# EEZ_DIB_BP3C_r3B2.net
KiCad netlist of a schematic drawn in EAGLE
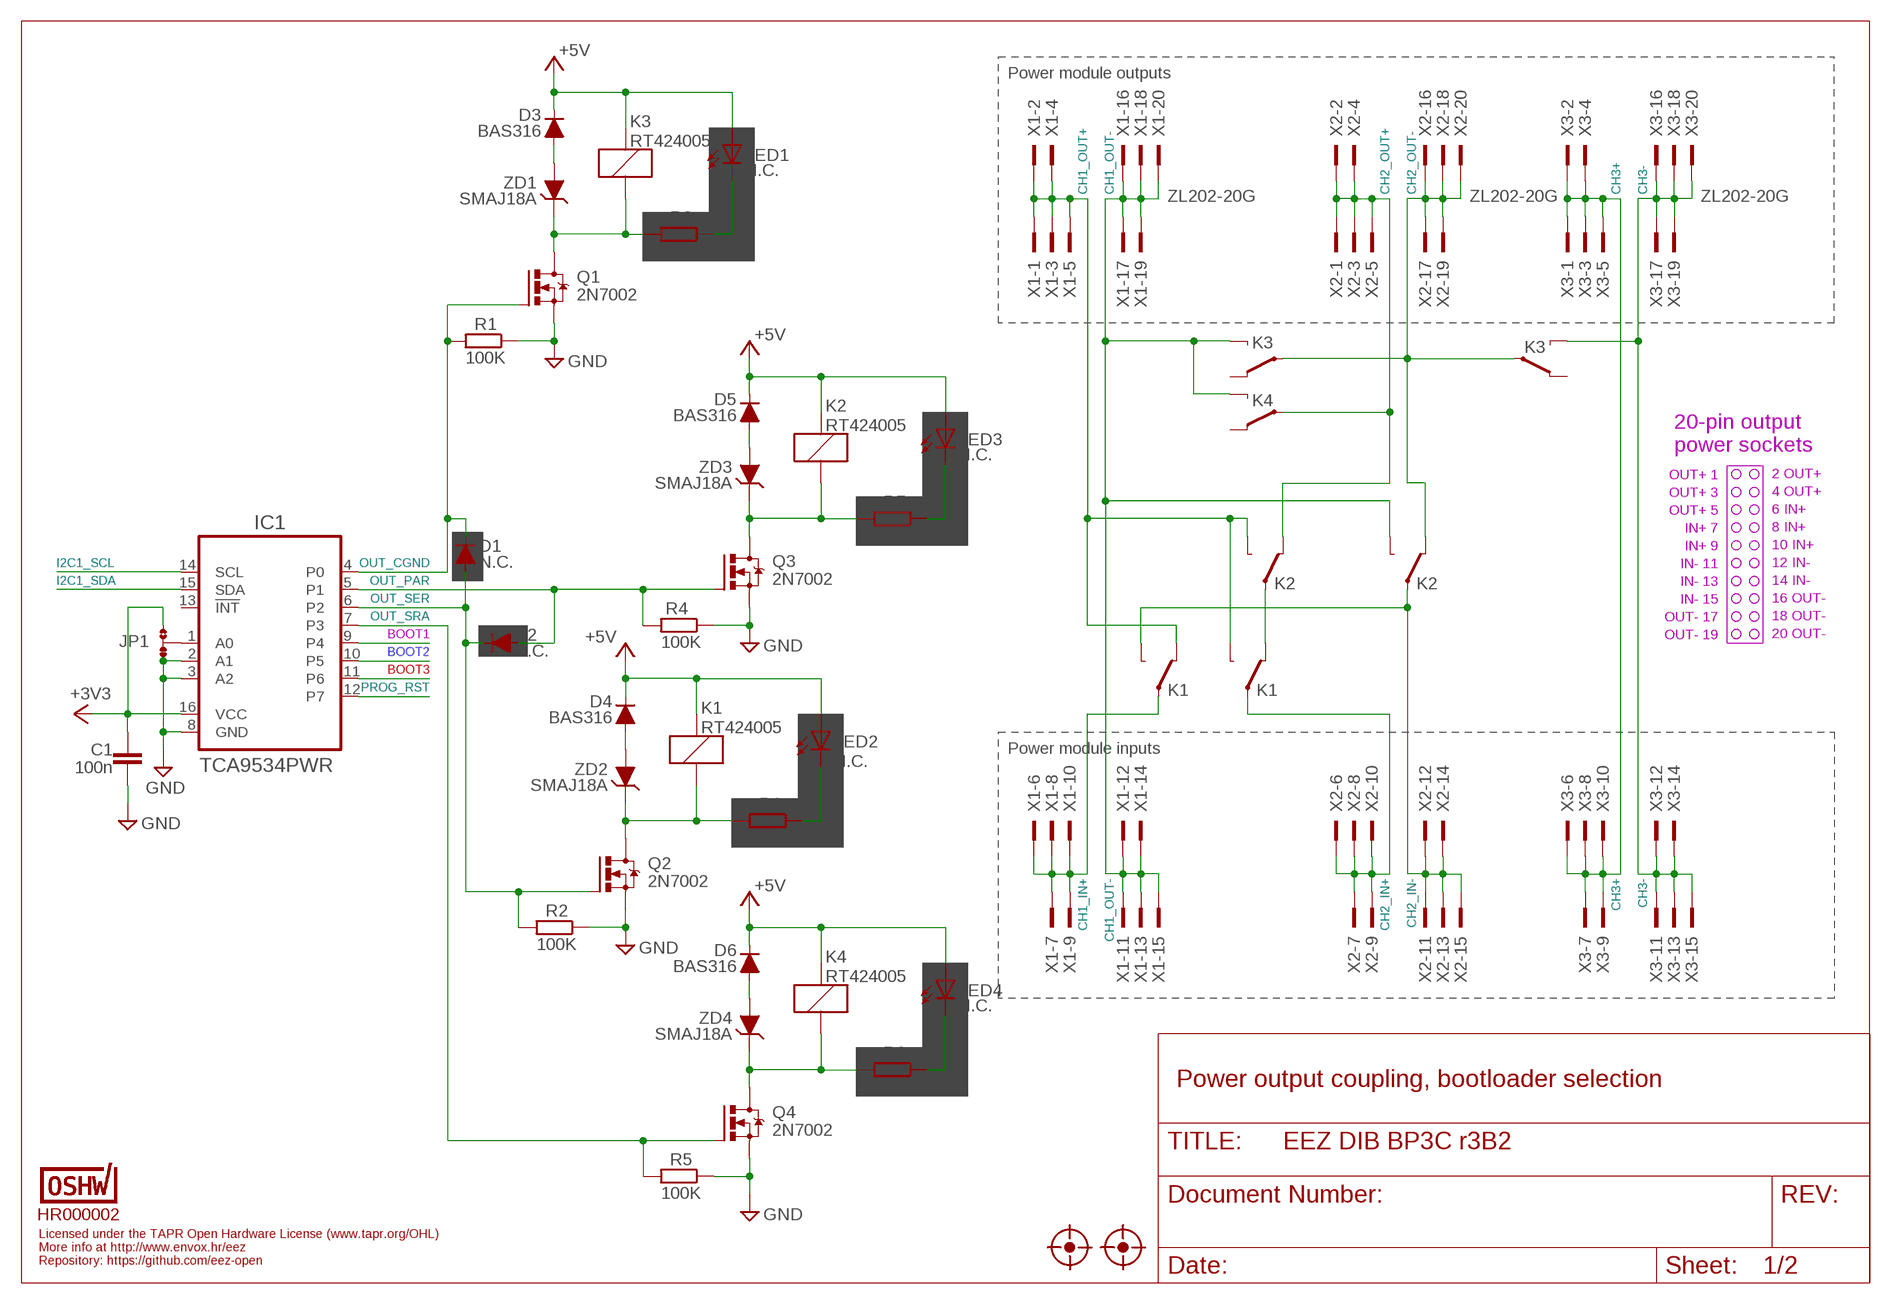
[diagram p0: schematic, sheet 1]
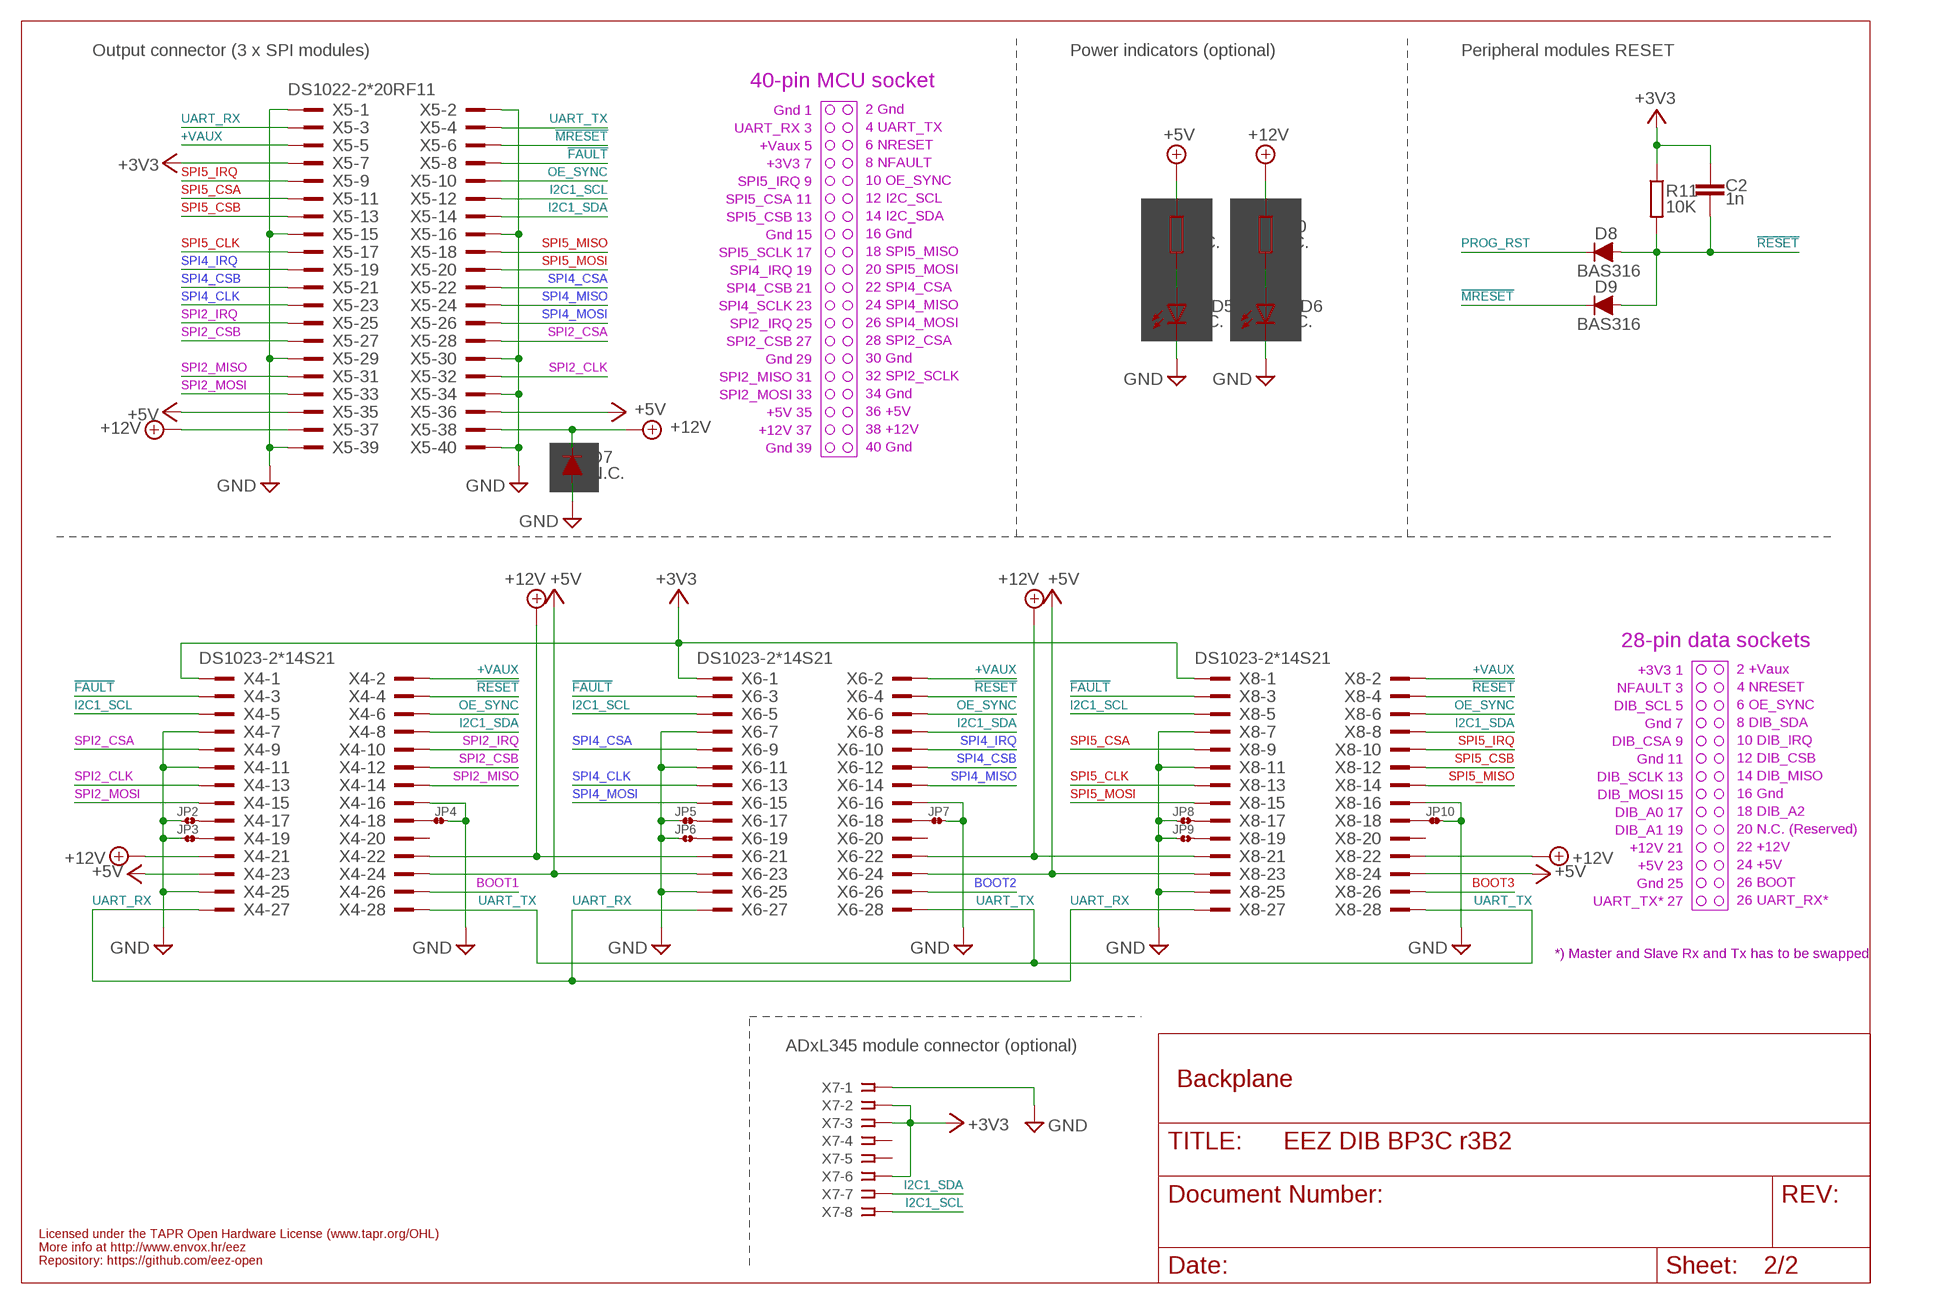
[diagram p1: schematic, sheet 2]

(export (version "E")
  (design (tool "Eeschema 10.0.6"))
  (components
    (comp (ref "C1")
      (value "100n")
      (footprint "eagle-import:C0603")
      (libsource (lib "eagle-import") (part "C-EUC0603"))
    )
    (comp (ref "D1")
      (value "N.C.")
      (footprint "eagle-import:SOD323-R")
      (libsource (lib "eagle-import") (part "DIODESOD323R"))
    )
    (comp (ref "D2")
      (value "N.C.")
      (footprint "eagle-import:SOD323-R")
      (libsource (lib "eagle-import") (part "DIODESOD323R"))
    )
    (comp (ref "D3")
      (value "BAS316")
      (footprint "eagle-import:SOD323-R")
      (libsource (lib "eagle-import") (part "DIODESOD323R"))
    )
    (comp (ref "D4")
      (value "BAS316")
      (footprint "eagle-import:SOD323-R")
      (libsource (lib "eagle-import") (part "DIODESOD323R"))
    )
    (comp (ref "D5")
      (value "BAS316")
      (footprint "eagle-import:SOD323-R")
      (libsource (lib "eagle-import") (part "DIODESOD323R"))
    )
    (comp (ref "D6")
      (value "BAS316")
      (footprint "eagle-import:SOD323-R")
      (libsource (lib "eagle-import") (part "DIODESOD323R"))
    )
    (comp (ref "FM1")
      (value "FIDUCIAL")
      (footprint "eagle-import:FIDUCIAL")
      (libsource (lib "eagle-import") (part "FIDUCIAL"))
    )
    (comp (ref "FM2")
      (value "FIDUCIAL")
      (footprint "eagle-import:FIDUCIAL")
      (libsource (lib "eagle-import") (part "FIDUCIAL"))
    )
    (comp (ref "IC1")
      (value "TCA9534PWR")
      (footprint "eagle-import:PW(R-PDSO-G16)")
      (libsource (lib "eagle-import") (part "TCA9534PWR"))
    )
    (comp (ref "JP1")
      (value "JP3-CUT")
      (footprint "eagle-import:JP3-CUT")
      (libsource (lib "eagle-import") (part "JP3-CUT"))
    )
    (comp (ref "K1")
      (value "RT424005")
      (footprint "eagle-import:RT-C_016A5_ROUND")
      (libsource (lib "eagle-import") (part "RELAY_RT314012-2"))
    )
    (comp (ref "K2")
      (value "RT424005")
      (footprint "eagle-import:RT-C_016A5_ROUND")
      (libsource (lib "eagle-import") (part "RELAY_RT314012-2"))
    )
    (comp (ref "K3")
      (value "RT424005")
      (footprint "eagle-import:RT-C_016A5_ROUND")
      (libsource (lib "eagle-import") (part "RELAY_RT314012-2"))
    )
    (comp (ref "K4")
      (value "RT424005")
      (footprint "eagle-import:RT-C_016A5_ROUND")
      (libsource (lib "eagle-import") (part "RELAY_RT314012-2"))
    )
    (comp (ref "LED1")
      (value "N.C.")
      (footprint "eagle-import:LED_0805")
      (libsource (lib "eagle-import") (part "LED0805"))
    )
    (comp (ref "LED2")
      (value "N.C.")
      (footprint "eagle-import:LED_0805")
      (libsource (lib "eagle-import") (part "LED0805"))
    )
    (comp (ref "LED3")
      (value "N.C.")
      (footprint "eagle-import:LED_0805")
      (libsource (lib "eagle-import") (part "LED0805"))
    )
    (comp (ref "LED4")
      (value "N.C.")
      (footprint "eagle-import:LED_0805")
      (libsource (lib "eagle-import") (part "LED0805"))
    )
    (comp (ref "OSHWA")
      (value "HR000002")
      (footprint "eagle-import:CERT-SMALL-SILK")
      (libsource (lib "eagle-import") (part "OSHWA-CERT-SMALL"))
    )
    (comp (ref "Q1")
      (value "2N7002")
      (footprint "eagle-import:SOT103P240X110-3N")
      (fields
        (field (name "MPN") "2N7002-7-F")
        (field (name "MPN_1") "2N7002-7-F")
        (field (name "OC_FARNELL") "1713823")
        (field (name "OC_NEWARK") "25R5679")
        (field (name "PACKAGE") "SOT-23-3")
        (field (name "SUPPLIER") "DIODES INC.")
      )
      (libsource (lib "eagle-import") (part "2N7002"))
    )
    (comp (ref "Q2")
      (value "2N7002")
      (footprint "eagle-import:SOT103P240X110-3N")
      (fields
        (field (name "MPN") "2N7002-7-F")
        (field (name "MPN_1") "2N7002-7-F")
        (field (name "OC_FARNELL") "1713823")
        (field (name "OC_NEWARK") "25R5679")
        (field (name "PACKAGE") "SOT-23-3")
        (field (name "SUPPLIER") "DIODES INC.")
      )
      (libsource (lib "eagle-import") (part "2N7002"))
    )
    (comp (ref "Q3")
      (value "2N7002")
      (footprint "eagle-import:SOT103P240X110-3N")
      (fields
        (field (name "MPN") "2N7002-7-F")
        (field (name "MPN_1") "2N7002-7-F")
        (field (name "OC_FARNELL") "1713823")
        (field (name "OC_NEWARK") "25R5679")
        (field (name "PACKAGE") "SOT-23-3")
        (field (name "SUPPLIER") "DIODES INC.")
      )
      (libsource (lib "eagle-import") (part "2N7002"))
    )
    (comp (ref "Q4")
      (value "2N7002")
      (footprint "eagle-import:SOT103P240X110-3N")
      (fields
        (field (name "MPN") "2N7002-7-F")
        (field (name "MPN_1") "2N7002-7-F")
        (field (name "OC_FARNELL") "1713823")
        (field (name "OC_NEWARK") "25R5679")
        (field (name "PACKAGE") "SOT-23-3")
        (field (name "SUPPLIER") "DIODES INC.")
      )
      (libsource (lib "eagle-import") (part "2N7002"))
    )
    (comp (ref "R1")
      (value "100K")
      (footprint "eagle-import:R0805")
      (libsource (lib "eagle-import") (part "R-EU_R0805"))
    )
    (comp (ref "R2")
      (value "100K")
      (footprint "eagle-import:R0805")
      (libsource (lib "eagle-import") (part "R-EU_R0805"))
    )
    (comp (ref "R3")
      (value "N.C.")
      (footprint "eagle-import:R0805")
      (libsource (lib "eagle-import") (part "R-EU_R0805"))
    )
    (comp (ref "R4")
      (value "100K")
      (footprint "eagle-import:R0805")
      (libsource (lib "eagle-import") (part "R-EU_R0805"))
    )
    (comp (ref "R5")
      (value "100K")
      (footprint "eagle-import:R0805")
      (libsource (lib "eagle-import") (part "R-EU_R0805"))
    )
    (comp (ref "R6")
      (value "N.C.")
      (footprint "eagle-import:R0805")
      (libsource (lib "eagle-import") (part "R-EU_R0805"))
    )
    (comp (ref "R7")
      (value "N.C.")
      (footprint "eagle-import:R0805")
      (libsource (lib "eagle-import") (part "R-EU_R0805"))
    )
    (comp (ref "R8")
      (value "N.C.")
      (footprint "eagle-import:R0805")
      (libsource (lib "eagle-import") (part "R-EU_R0805"))
    )
    (comp (ref "X1")
      (value "ZL202-20G")
      (footprint "eagle-import:DS1021-2_10SF11")
      (libsource (lib "eagle-import") (part "DS1021-210SF11"))
    )
    (comp (ref "X2")
      (value "ZL202-20G")
      (footprint "eagle-import:DS1021-2_10SF11")
      (libsource (lib "eagle-import") (part "DS1021-210SF11"))
    )
    (comp (ref "X3")
      (value "ZL202-20G")
      (footprint "eagle-import:DS1021-2_10SF11")
      (libsource (lib "eagle-import") (part "DS1021-210SF11"))
    )
    (comp (ref "ZD1")
      (value "SMAJ18A")
      (footprint "eagle-import:DO214AC")
      (libsource (lib "eagle-import") (part "PSMAXX"))
    )
    (comp (ref "ZD2")
      (value "SMAJ18A")
      (footprint "eagle-import:DO214AC")
      (libsource (lib "eagle-import") (part "PSMAXX"))
    )
    (comp (ref "ZD3")
      (value "SMAJ18A")
      (footprint "eagle-import:DO214AC")
      (libsource (lib "eagle-import") (part "PSMAXX"))
    )
    (comp (ref "ZD4")
      (value "SMAJ18A")
      (footprint "eagle-import:DO214AC")
      (libsource (lib "eagle-import") (part "PSMAXX"))
    )
    (comp (ref "C2")
      (value "1n")
      (footprint "eagle-import:C0805")
      (libsource (lib "eagle-import") (part "C-EUC0805"))
    )
    (comp (ref "D7")
      (value "N.C.")
      (footprint "eagle-import:DO214AA")
      (libsource (lib "eagle-import") (part "MyLib6_DIODEDO214AA"))
    )
    (comp (ref "D8")
      (value "BAS316")
      (footprint "eagle-import:SOD323-R")
      (libsource (lib "eagle-import") (part "DIODESOD323R"))
    )
    (comp (ref "D9")
      (value "BAS316")
      (footprint "eagle-import:SOD323-R")
      (libsource (lib "eagle-import") (part "DIODESOD323R"))
    )
    (comp (ref "JP2")
      (value "JP2-CUT")
      (footprint "eagle-import:JP2-CUT")
      (libsource (lib "eagle-import") (part "JP2-CUT"))
    )
    (comp (ref "JP3")
      (value "JP2-NOCUT")
      (footprint "eagle-import:JP2-NOCUT")
      (libsource (lib "eagle-import") (part "JP2-NOCUT"))
    )
    (comp (ref "JP4")
      (value "JP2-NOCUT")
      (footprint "eagle-import:JP2-NOCUT")
      (libsource (lib "eagle-import") (part "JP2-NOCUT"))
    )
    (comp (ref "JP5")
      (value "JP2-NOCUT")
      (footprint "eagle-import:JP2-NOCUT")
      (libsource (lib "eagle-import") (part "JP2-NOCUT"))
    )
    (comp (ref "JP6")
      (value "JP2-CUT")
      (footprint "eagle-import:JP2-CUT")
      (libsource (lib "eagle-import") (part "JP2-CUT"))
    )
    (comp (ref "JP7")
      (value "JP2-NOCUT")
      (footprint "eagle-import:JP2-NOCUT")
      (libsource (lib "eagle-import") (part "JP2-NOCUT"))
    )
    (comp (ref "JP8")
      (value "JP2-CUT")
      (footprint "eagle-import:JP2-CUT")
      (libsource (lib "eagle-import") (part "JP2-CUT"))
    )
    (comp (ref "JP9")
      (value "JP2-CUT")
      (footprint "eagle-import:JP2-CUT")
      (libsource (lib "eagle-import") (part "JP2-CUT"))
    )
    (comp (ref "JP10")
      (value "JP2-NOCUT")
      (footprint "eagle-import:JP2-NOCUT")
      (libsource (lib "eagle-import") (part "JP2-NOCUT"))
    )
    (comp (ref "LED5")
      (value "N.C.")
      (footprint "eagle-import:LED_0805")
      (libsource (lib "eagle-import") (part "LED0805"))
    )
    (comp (ref "LED6")
      (value "N.C.")
      (footprint "eagle-import:LED_0805")
      (libsource (lib "eagle-import") (part "LED0805"))
    )
    (comp (ref "R9")
      (value "N.C.")
      (footprint "eagle-import:R0805")
      (libsource (lib "eagle-import") (part "R-EU_R0805"))
    )
    (comp (ref "R10")
      (value "N.C.")
      (footprint "eagle-import:R0805")
      (libsource (lib "eagle-import") (part "R-EU_R0805"))
    )
    (comp (ref "R11")
      (value "10K")
      (footprint "eagle-import:R0805")
      (libsource (lib "eagle-import") (part "R-EU_R0805"))
    )
    (comp (ref "X4")
      (value "DS1023-2*14S21")
      (footprint "eagle-import:TSW-114-07-F-D")
      (libsource (lib "eagle-import") (part "TSW-114-07-F-D"))
    )
    (comp (ref "X5")
      (value "DS1022-2*20RF11")
      (footprint "eagle-import:ZL212-40KG")
      (libsource (lib "eagle-import") (part "ZL212-40KG"))
    )
    (comp (ref "X6")
      (value "DS1023-2*14S21")
      (footprint "eagle-import:TSW-114-07-F-D")
      (libsource (lib "eagle-import") (part "TSW-114-07-F-D"))
    )
    (comp (ref "X7")
      (value "N.C.")
      (footprint "eagle-import:SSW-108-02-S-S")
      (fields (field (name "MPN") "SSW-108-02-S-S"))
      (libsource (lib "eagle-import") (part "SSW-108-02-S-S"))
    )
    (comp (ref "X8")
      (value "DS1023-2*14S21")
      (footprint "eagle-import:TSW-114-07-F-D")
      (libsource (lib "eagle-import") (part "TSW-114-07-F-D"))
    )
  )
  (nets
    (net (code "1") (name "+3V3") (class "Default")
      (node (ref "C1") (pin "1") (pinfunction "1_1") (pintype "passive"))
      (node (ref "C2") (pin "2") (pinfunction "2_2") (pintype "passive"))
      (node (ref "IC1") (pin "16") (pinfunction "VCC_16") (pintype "passive"))
      (node (ref "JP1") (pin "NO") (pinfunction "NO_NO") (pintype "passive"))
      (node (ref "R11") (pin "1") (pinfunction "1_1") (pintype "passive"))
      (node (ref "X4") (pin "1") (pinfunction "1_1") (pintype "passive"))
      (node (ref "X5") (pin "7") (pinfunction "1_7") (pintype "passive"))
      (node (ref "X6") (pin "1") (pinfunction "1_1") (pintype "passive"))
      (node (ref "X7") (pin "2") (pinfunction "1_2") (pintype "passive"))
      (node (ref "X7") (pin "3") (pinfunction "1_3") (pintype "passive"))
      (node (ref "X7") (pin "6") (pinfunction "1_6") (pintype "passive"))
      (node (ref "X8") (pin "1") (pinfunction "1_1") (pintype "passive"))
    )
    (net (code "2") (name "+5V") (class "Default")
      (node (ref "D3") (pin "C") (pinfunction "C_C") (pintype "passive"))
      (node (ref "D4") (pin "C") (pinfunction "C_C") (pintype "passive"))
      (node (ref "D5") (pin "C") (pinfunction "C_C") (pintype "passive"))
      (node (ref "D6") (pin "C") (pinfunction "C_C") (pintype "passive"))
      (node (ref "K1") (pin "A2") (pinfunction "C1_A2") (pintype "passive"))
      (node (ref "K2") (pin "A2") (pinfunction "C1_A2") (pintype "passive"))
      (node (ref "K3") (pin "A2") (pinfunction "C1_A2") (pintype "passive"))
      (node (ref "K4") (pin "A2") (pinfunction "C1_A2") (pintype "passive"))
      (node (ref "LED1") (pin "A") (pinfunction "A_A") (pintype "passive"))
      (node (ref "LED2") (pin "A") (pinfunction "A_A") (pintype "passive"))
      (node (ref "LED3") (pin "A") (pinfunction "A_A") (pintype "passive"))
      (node (ref "LED4") (pin "A") (pinfunction "A_A") (pintype "passive"))
      (node (ref "R9") (pin "1") (pinfunction "1_1") (pintype "passive"))
      (node (ref "X4") (pin "23") (pinfunction "1_23") (pintype "passive"))
      (node (ref "X4") (pin "24") (pinfunction "1_24") (pintype "passive"))
      (node (ref "X5") (pin "35") (pinfunction "1_35") (pintype "passive"))
      (node (ref "X5") (pin "36") (pinfunction "1_36") (pintype "passive"))
      (node (ref "X6") (pin "23") (pinfunction "1_23") (pintype "passive"))
      (node (ref "X6") (pin "24") (pinfunction "1_24") (pintype "passive"))
      (node (ref "X8") (pin "23") (pinfunction "1_23") (pintype "passive"))
      (node (ref "X8") (pin "24") (pinfunction "1_24") (pintype "passive"))
    )
    (net (code "3") (name "+12V") (class "Default")
      (node (ref "D7") (pin "C") (pinfunction "C_C") (pintype "passive"))
      (node (ref "R10") (pin "1") (pinfunction "1_1") (pintype "passive"))
      (node (ref "X4") (pin "21") (pinfunction "1_21") (pintype "passive"))
      (node (ref "X4") (pin "22") (pinfunction "1_22") (pintype "passive"))
      (node (ref "X5") (pin "37") (pinfunction "1_37") (pintype "passive"))
      (node (ref "X5") (pin "38") (pinfunction "1_38") (pintype "passive"))
      (node (ref "X6") (pin "21") (pinfunction "1_21") (pintype "passive"))
      (node (ref "X6") (pin "22") (pinfunction "1_22") (pintype "passive"))
      (node (ref "X8") (pin "21") (pinfunction "1_21") (pintype "passive"))
      (node (ref "X8") (pin "22") (pinfunction "1_22") (pintype "passive"))
    )
    (net (code "4") (name "+VAUX") (class "Default")
      (node (ref "X4") (pin "2") (pinfunction "1_2") (pintype "passive"))
      (node (ref "X5") (pin "5") (pinfunction "1_5") (pintype "passive"))
      (node (ref "X6") (pin "2") (pinfunction "1_2") (pintype "passive"))
      (node (ref "X8") (pin "2") (pinfunction "1_2") (pintype "passive"))
    )
    (net (code "5") (name "BOOT1") (class "Default")
      (node (ref "IC1") (pin "9") (pinfunction "P4_9") (pintype "bidirectional"))
      (node (ref "X4") (pin "26") (pinfunction "1_26") (pintype "passive"))
    )
    (net (code "6") (name "BOOT2") (class "Default")
      (node (ref "IC1") (pin "10") (pinfunction "P5_10") (pintype "bidirectional"))
      (node (ref "X6") (pin "26") (pinfunction "1_26") (pintype "passive"))
    )
    (net (code "7") (name "BOOT3") (class "Default")
      (node (ref "IC1") (pin "11") (pinfunction "P6_11") (pintype "bidirectional"))
      (node (ref "X8") (pin "26") (pinfunction "1_26") (pintype "passive"))
    )
    (net (code "8") (name "CH1_IN+") (class "Default")
      (node (ref "K1") (pin "11A") (pinfunction "P_11A") (pintype "passive"))
      (node (ref "X1") (pin "10") (pinfunction "1_10") (pintype "passive"))
      (node (ref "X1") (pin "6") (pinfunction "1_6") (pintype "passive"))
      (node (ref "X1") (pin "7") (pinfunction "1_7") (pintype "passive"))
      (node (ref "X1") (pin "8") (pinfunction "1_8") (pintype "passive"))
      (node (ref "X1") (pin "9") (pinfunction "1_9") (pintype "passive"))
    )
    (net (code "9") (name "CH1_OUT+") (class "Default")
      (node (ref "K1") (pin "12A") (pinfunction "S_12A") (pintype "passive"))
      (node (ref "K1") (pin "14B") (pinfunction "O_14B") (pintype "passive"))
      (node (ref "K2") (pin "14A") (pinfunction "O_14A") (pintype "passive"))
      (node (ref "X1") (pin "1") (pinfunction "1_1") (pintype "passive"))
      (node (ref "X1") (pin "2") (pinfunction "1_2") (pintype "passive"))
      (node (ref "X1") (pin "3") (pinfunction "1_3") (pintype "passive"))
      (node (ref "X1") (pin "4") (pinfunction "1_4") (pintype "passive"))
      (node (ref "X1") (pin "5") (pinfunction "1_5") (pintype "passive"))
    )
    (net (code "10") (name "CH1_OUT-") (class "Default")
      (node (ref "K2") (pin "14B") (pinfunction "O_14B") (pintype "passive"))
      (node (ref "K3") (pin "14A") (pinfunction "O_14A") (pintype "passive"))
      (node (ref "K4") (pin "14A") (pinfunction "O_14A") (pintype "passive"))
      (node (ref "X1") (pin "11") (pinfunction "1_11") (pintype "passive"))
      (node (ref "X1") (pin "12") (pinfunction "1_12") (pintype "passive"))
      (node (ref "X1") (pin "13") (pinfunction "1_13") (pintype "passive"))
      (node (ref "X1") (pin "14") (pinfunction "1_14") (pintype "passive"))
      (node (ref "X1") (pin "15") (pinfunction "1_15") (pintype "passive"))
      (node (ref "X1") (pin "16") (pinfunction "1_16") (pintype "passive"))
      (node (ref "X1") (pin "17") (pinfunction "1_17") (pintype "passive"))
      (node (ref "X1") (pin "18") (pinfunction "1_18") (pintype "passive"))
      (node (ref "X1") (pin "19") (pinfunction "1_19") (pintype "passive"))
      (node (ref "X1") (pin "20") (pinfunction "1_20") (pintype "passive"))
    )
    (net (code "11") (name "CH2_IN+") (class "Default")
      (node (ref "K1") (pin "11B") (pinfunction "P_11B") (pintype "passive"))
      (node (ref "X2") (pin "10") (pinfunction "1_10") (pintype "passive"))
      (node (ref "X2") (pin "6") (pinfunction "1_6") (pintype "passive"))
      (node (ref "X2") (pin "7") (pinfunction "1_7") (pintype "passive"))
      (node (ref "X2") (pin "8") (pinfunction "1_8") (pintype "passive"))
      (node (ref "X2") (pin "9") (pinfunction "1_9") (pintype "passive"))
    )
    (net (code "12") (name "CH2_IN-") (class "Default")
      (node (ref "K1") (pin "14A") (pinfunction "O_14A") (pintype "passive"))
      (node (ref "K2") (pin "11B") (pinfunction "P_11B") (pintype "passive"))
      (node (ref "X2") (pin "11") (pinfunction "1_11") (pintype "passive"))
      (node (ref "X2") (pin "12") (pinfunction "1_12") (pintype "passive"))
      (node (ref "X2") (pin "13") (pinfunction "1_13") (pintype "passive"))
      (node (ref "X2") (pin "14") (pinfunction "1_14") (pintype "passive"))
      (node (ref "X2") (pin "15") (pinfunction "1_15") (pintype "passive"))
    )
    (net (code "13") (name "CH2_OUT+") (class "Default")
      (node (ref "K2") (pin "12A") (pinfunction "S_12A") (pintype "passive"))
      (node (ref "K4") (pin "11A") (pinfunction "P_11A") (pintype "passive"))
      (node (ref "X2") (pin "1") (pinfunction "1_1") (pintype "passive"))
      (node (ref "X2") (pin "2") (pinfunction "1_2") (pintype "passive"))
      (node (ref "X2") (pin "3") (pinfunction "1_3") (pintype "passive"))
      (node (ref "X2") (pin "4") (pinfunction "1_4") (pintype "passive"))
      (node (ref "X2") (pin "5") (pinfunction "1_5") (pintype "passive"))
    )
    (net (code "14") (name "CH2_OUT-") (class "Default")
      (node (ref "K2") (pin "12B") (pinfunction "S_12B") (pintype "passive"))
      (node (ref "K3") (pin "11A") (pinfunction "P_11A") (pintype "passive"))
      (node (ref "K3") (pin "11B") (pinfunction "P_11B") (pintype "passive"))
      (node (ref "X2") (pin "16") (pinfunction "1_16") (pintype "passive"))
      (node (ref "X2") (pin "17") (pinfunction "1_17") (pintype "passive"))
      (node (ref "X2") (pin "18") (pinfunction "1_18") (pintype "passive"))
      (node (ref "X2") (pin "19") (pinfunction "1_19") (pintype "passive"))
      (node (ref "X2") (pin "20") (pinfunction "1_20") (pintype "passive"))
    )
    (net (code "15") (name "CH3+") (class "Default")
      (node (ref "X3") (pin "1") (pinfunction "1_1") (pintype "passive"))
      (node (ref "X3") (pin "10") (pinfunction "1_10") (pintype "passive"))
      (node (ref "X3") (pin "2") (pinfunction "1_2") (pintype "passive"))
      (node (ref "X3") (pin "3") (pinfunction "1_3") (pintype "passive"))
      (node (ref "X3") (pin "4") (pinfunction "1_4") (pintype "passive"))
      (node (ref "X3") (pin "5") (pinfunction "1_5") (pintype "passive"))
      (node (ref "X3") (pin "6") (pinfunction "1_6") (pintype "passive"))
      (node (ref "X3") (pin "7") (pinfunction "1_7") (pintype "passive"))
      (node (ref "X3") (pin "8") (pinfunction "1_8") (pintype "passive"))
      (node (ref "X3") (pin "9") (pinfunction "1_9") (pintype "passive"))
    )
    (net (code "16") (name "CH3-") (class "Default")
      (node (ref "K3") (pin "14B") (pinfunction "O_14B") (pintype "passive"))
      (node (ref "X3") (pin "11") (pinfunction "1_11") (pintype "passive"))
      (node (ref "X3") (pin "12") (pinfunction "1_12") (pintype "passive"))
      (node (ref "X3") (pin "13") (pinfunction "1_13") (pintype "passive"))
      (node (ref "X3") (pin "14") (pinfunction "1_14") (pintype "passive"))
      (node (ref "X3") (pin "15") (pinfunction "1_15") (pintype "passive"))
      (node (ref "X3") (pin "16") (pinfunction "1_16") (pintype "passive"))
      (node (ref "X3") (pin "17") (pinfunction "1_17") (pintype "passive"))
      (node (ref "X3") (pin "18") (pinfunction "1_18") (pintype "passive"))
      (node (ref "X3") (pin "19") (pinfunction "1_19") (pintype "passive"))
      (node (ref "X3") (pin "20") (pinfunction "1_20") (pintype "passive"))
    )
    (net (code "17") (name "GND") (class "Default")
      (node (ref "C1") (pin "2") (pinfunction "2_2") (pintype "passive"))
      (node (ref "D7") (pin "A") (pinfunction "A_A") (pintype "passive"))
      (node (ref "IC1") (pin "2") (pinfunction "A1_2") (pintype "input"))
      (node (ref "IC1") (pin "3") (pinfunction "A2_3") (pintype "input"))
      (node (ref "IC1") (pin "8") (pinfunction "GND_8") (pintype "passive"))
      (node (ref "JP1") (pin "NC") (pinfunction "NC_NC") (pintype "passive"))
      (node (ref "JP10") (pin "2") (pinfunction "2_2") (pintype "passive"))
      (node (ref "JP2") (pin "1") (pinfunction "1_1") (pintype "passive"))
      (node (ref "JP3") (pin "1") (pinfunction "1_1") (pintype "passive"))
      (node (ref "JP4") (pin "2") (pinfunction "2_2") (pintype "passive"))
      (node (ref "JP5") (pin "1") (pinfunction "1_1") (pintype "passive"))
      (node (ref "JP6") (pin "1") (pinfunction "1_1") (pintype "passive"))
      (node (ref "JP7") (pin "2") (pinfunction "2_2") (pintype "passive"))
      (node (ref "JP8") (pin "1") (pinfunction "1_1") (pintype "passive"))
      (node (ref "JP9") (pin "1") (pinfunction "1_1") (pintype "passive"))
      (node (ref "LED5") (pin "C") (pinfunction "C_C") (pintype "passive"))
      (node (ref "LED6") (pin "C") (pinfunction "C_C") (pintype "passive"))
      (node (ref "Q1") (pin "2") (pinfunction "S_2") (pintype "passive"))
      (node (ref "Q2") (pin "2") (pinfunction "S_2") (pintype "passive"))
      (node (ref "Q3") (pin "2") (pinfunction "S_2") (pintype "passive"))
      (node (ref "Q4") (pin "2") (pinfunction "S_2") (pintype "passive"))
      (node (ref "R1") (pin "1") (pinfunction "1_1") (pintype "passive"))
      (node (ref "R2") (pin "1") (pinfunction "1_1") (pintype "passive"))
      (node (ref "R4") (pin "1") (pinfunction "1_1") (pintype "passive"))
      (node (ref "R5") (pin "1") (pinfunction "1_1") (pintype "passive"))
      (node (ref "X4") (pin "11") (pinfunction "1_11") (pintype "passive"))
      (node (ref "X4") (pin "16") (pinfunction "1_16") (pintype "passive"))
      (node (ref "X4") (pin "25") (pinfunction "1_25") (pintype "passive"))
      (node (ref "X4") (pin "7") (pinfunction "1_7") (pintype "passive"))
      (node (ref "X5") (pin "1") (pinfunction "1_1") (pintype "passive"))
      (node (ref "X5") (pin "15") (pinfunction "1_15") (pintype "passive"))
      (node (ref "X5") (pin "16") (pinfunction "1_16") (pintype "passive"))
      (node (ref "X5") (pin "2") (pinfunction "1_2") (pintype "passive"))
      (node (ref "X5") (pin "29") (pinfunction "1_29") (pintype "passive"))
      (node (ref "X5") (pin "30") (pinfunction "1_30") (pintype "passive"))
      (node (ref "X5") (pin "34") (pinfunction "1_34") (pintype "passive"))
      (node (ref "X5") (pin "39") (pinfunction "1_39") (pintype "passive"))
      (node (ref "X5") (pin "40") (pinfunction "1_40") (pintype "passive"))
      (node (ref "X6") (pin "11") (pinfunction "1_11") (pintype "passive"))
      (node (ref "X6") (pin "16") (pinfunction "1_16") (pintype "passive"))
      (node (ref "X6") (pin "25") (pinfunction "1_25") (pintype "passive"))
      (node (ref "X6") (pin "7") (pinfunction "1_7") (pintype "passive"))
      (node (ref "X7") (pin "1") (pinfunction "1_1") (pintype "passive"))
      (node (ref "X8") (pin "11") (pinfunction "1_11") (pintype "passive"))
      (node (ref "X8") (pin "16") (pinfunction "1_16") (pintype "passive"))
      (node (ref "X8") (pin "25") (pinfunction "1_25") (pintype "passive"))
      (node (ref "X8") (pin "7") (pinfunction "1_7") (pintype "passive"))
    )
    (net (code "18") (name "I2C1_SCL") (class "Default")
      (node (ref "IC1") (pin "14") (pinfunction "SCL_14") (pintype "input"))
      (node (ref "X4") (pin "5") (pinfunction "1_5") (pintype "passive"))
      (node (ref "X5") (pin "12") (pinfunction "1_12") (pintype "passive"))
      (node (ref "X6") (pin "5") (pinfunction "1_5") (pintype "passive"))
      (node (ref "X7") (pin "8") (pinfunction "1_8") (pintype "passive"))
      (node (ref "X8") (pin "5") (pinfunction "1_5") (pintype "passive"))
    )
    (net (code "19") (name "I2C1_SDA") (class "Default")
      (node (ref "IC1") (pin "15") (pinfunction "SDA_15") (pintype "bidirectional"))
      (node (ref "X4") (pin "8") (pinfunction "1_8") (pintype "passive"))
      (node (ref "X5") (pin "14") (pinfunction "1_14") (pintype "passive"))
      (node (ref "X6") (pin "8") (pinfunction "1_8") (pintype "passive"))
      (node (ref "X7") (pin "7") (pinfunction "1_7") (pintype "passive"))
      (node (ref "X8") (pin "8") (pinfunction "1_8") (pintype "passive"))
    )
    (net (code "20") (name "Net-(D3-PadA)") (class "Default")
      (node (ref "D3") (pin "A") (pinfunction "A_A") (pintype "passive"))
      (node (ref "ZD1") (pin "A") (pinfunction "A_A") (pintype "passive"))
    )
    (net (code "21") (name "Net-(D4-PadA)") (class "Default")
      (node (ref "D4") (pin "A") (pinfunction "A_A") (pintype "passive"))
      (node (ref "ZD2") (pin "A") (pinfunction "A_A") (pintype "passive"))
    )
    (net (code "22") (name "Net-(D5-PadA)") (class "Default")
      (node (ref "D5") (pin "A") (pinfunction "A_A") (pintype "passive"))
      (node (ref "ZD3") (pin "A") (pinfunction "A_A") (pintype "passive"))
    )
    (net (code "23") (name "Net-(D6-PadA)") (class "Default")
      (node (ref "D6") (pin "A") (pinfunction "A_A") (pintype "passive"))
      (node (ref "ZD4") (pin "A") (pinfunction "A_A") (pintype "passive"))
    )
    (net (code "24") (name "Net-(IC1-A0)") (class "Default")
      (node (ref "IC1") (pin "1") (pinfunction "A0_1") (pintype "input"))
      (node (ref "JP1") (pin "COM") (pinfunction "COM_COM") (pintype "passive"))
    )
    (net (code "25") (name "Net-(K1B-S)") (class "Default")
      (node (ref "K1") (pin "12B") (pinfunction "S_12B") (pintype "passive"))
      (node (ref "K2") (pin "11A") (pinfunction "P_11A") (pintype "passive"))
    )
    (net (code "26") (name "Net-(K1C-C2)") (class "Default")
      (node (ref "K1") (pin "A1") (pinfunction "C2_A1") (pintype "passive"))
      (node (ref "Q2") (pin "3") (pinfunction "D_3") (pintype "passive"))
      (node (ref "R6") (pin "2") (pinfunction "2_2") (pintype "passive"))
      (node (ref "ZD2") (pin "C") (pinfunction "C_C") (pintype "passive"))
    )
    (net (code "27") (name "Net-(K2C-C2)") (class "Default")
      (node (ref "K2") (pin "A1") (pinfunction "C2_A1") (pintype "passive"))
      (node (ref "Q3") (pin "3") (pinfunction "D_3") (pintype "passive"))
      (node (ref "R7") (pin "2") (pinfunction "2_2") (pintype "passive"))
      (node (ref "ZD3") (pin "C") (pinfunction "C_C") (pintype "passive"))
    )
    (net (code "28") (name "Net-(K3C-C2)") (class "Default")
      (node (ref "K3") (pin "A1") (pinfunction "C2_A1") (pintype "passive"))
      (node (ref "Q1") (pin "3") (pinfunction "D_3") (pintype "passive"))
      (node (ref "R3") (pin "2") (pinfunction "2_2") (pintype "passive"))
      (node (ref "ZD1") (pin "C") (pinfunction "C_C") (pintype "passive"))
    )
    (net (code "29") (name "Net-(K4C-C2)") (class "Default")
      (node (ref "K4") (pin "A1") (pinfunction "C2_A1") (pintype "passive"))
      (node (ref "Q4") (pin "3") (pinfunction "D_3") (pintype "passive"))
      (node (ref "R8") (pin "2") (pinfunction "2_2") (pintype "passive"))
      (node (ref "ZD4") (pin "C") (pinfunction "C_C") (pintype "passive"))
    )
    (net (code "30") (name "Net-(LED1-PadC)") (class "Default")
      (node (ref "LED1") (pin "C") (pinfunction "C_C") (pintype "passive"))
      (node (ref "R3") (pin "1") (pinfunction "1_1") (pintype "passive"))
    )
    (net (code "31") (name "Net-(LED2-PadC)") (class "Default")
      (node (ref "LED2") (pin "C") (pinfunction "C_C") (pintype "passive"))
      (node (ref "R6") (pin "1") (pinfunction "1_1") (pintype "passive"))
    )
    (net (code "32") (name "Net-(LED3-PadC)") (class "Default")
      (node (ref "LED3") (pin "C") (pinfunction "C_C") (pintype "passive"))
      (node (ref "R7") (pin "1") (pinfunction "1_1") (pintype "passive"))
    )
    (net (code "33") (name "Net-(LED4-PadC)") (class "Default")
      (node (ref "LED4") (pin "C") (pinfunction "C_C") (pintype "passive"))
      (node (ref "R8") (pin "1") (pinfunction "1_1") (pintype "passive"))
    )
    (net (code "34") (name "Net-(LED5-PadA)") (class "Default")
      (node (ref "LED5") (pin "A") (pinfunction "A_A") (pintype "passive"))
      (node (ref "R9") (pin "2") (pinfunction "2_2") (pintype "passive"))
    )
    (net (code "35") (name "Net-(LED6-PadA)") (class "Default")
      (node (ref "LED6") (pin "A") (pinfunction "A_A") (pintype "passive"))
      (node (ref "R10") (pin "2") (pinfunction "2_2") (pintype "passive"))
    )
    (net (code "36") (name "Net-(X4I-1)") (class "Default")
      (node (ref "JP2") (pin "2") (pinfunction "2_2") (pintype "passive"))
      (node (ref "X4") (pin "17") (pinfunction "1_17") (pintype "passive"))
    )
    (net (code "37") (name "Net-(X4J-1)") (class "Default")
      (node (ref "JP4") (pin "1") (pinfunction "1_1") (pintype "passive"))
      (node (ref "X4") (pin "18") (pinfunction "1_18") (pintype "passive"))
    )
    (net (code "38") (name "Net-(X4K-1)") (class "Default")
      (node (ref "JP3") (pin "2") (pinfunction "2_2") (pintype "passive"))
      (node (ref "X4") (pin "19") (pinfunction "1_19") (pintype "passive"))
    )
    (net (code "39") (name "Net-(X6I-1)") (class "Default")
      (node (ref "JP5") (pin "2") (pinfunction "2_2") (pintype "passive"))
      (node (ref "X6") (pin "17") (pinfunction "1_17") (pintype "passive"))
    )
    (net (code "40") (name "Net-(X6J-1)") (class "Default")
      (node (ref "JP7") (pin "1") (pinfunction "1_1") (pintype "passive"))
      (node (ref "X6") (pin "18") (pinfunction "1_18") (pintype "passive"))
    )
    (net (code "41") (name "Net-(X6K-1)") (class "Default")
      (node (ref "JP6") (pin "2") (pinfunction "2_2") (pintype "passive"))
      (node (ref "X6") (pin "19") (pinfunction "1_19") (pintype "passive"))
    )
    (net (code "42") (name "Net-(X8I-1)") (class "Default")
      (node (ref "JP8") (pin "2") (pinfunction "2_2") (pintype "passive"))
      (node (ref "X8") (pin "17") (pinfunction "1_17") (pintype "passive"))
    )
    (net (code "43") (name "Net-(X8J-1)") (class "Default")
      (node (ref "JP10") (pin "1") (pinfunction "1_1") (pintype "passive"))
      (node (ref "X8") (pin "18") (pinfunction "1_18") (pintype "passive"))
    )
    (net (code "44") (name "Net-(X8K-1)") (class "Default")
      (node (ref "JP9") (pin "2") (pinfunction "2_2") (pintype "passive"))
      (node (ref "X8") (pin "19") (pinfunction "1_19") (pintype "passive"))
    )
    (net (code "45") (name "OE_SYNC") (class "Default")
      (node (ref "X4") (pin "6") (pinfunction "1_6") (pintype "passive"))
      (node (ref "X5") (pin "10") (pinfunction "1_10") (pintype "passive"))
      (node (ref "X6") (pin "6") (pinfunction "1_6") (pintype "passive"))
      (node (ref "X8") (pin "6") (pinfunction "1_6") (pintype "passive"))
    )
    (net (code "46") (name "OUT_CGND") (class "Default")
      (node (ref "D1") (pin "C") (pinfunction "C_C") (pintype "passive"))
      (node (ref "IC1") (pin "4") (pinfunction "P0_4") (pintype "bidirectional"))
      (node (ref "Q1") (pin "1") (pinfunction "G_1") (pintype "passive"))
      (node (ref "R1") (pin "2") (pinfunction "2_2") (pintype "passive"))
    )
    (net (code "47") (name "OUT_PAR") (class "Default")
      (node (ref "D2") (pin "A") (pinfunction "A_A") (pintype "passive"))
      (node (ref "IC1") (pin "5") (pinfunction "P1_5") (pintype "bidirectional"))
      (node (ref "Q3") (pin "1") (pinfunction "G_1") (pintype "passive"))
      (node (ref "R4") (pin "2") (pinfunction "2_2") (pintype "passive"))
    )
    (net (code "48") (name "OUT_SER") (class "Default")
      (node (ref "D1") (pin "A") (pinfunction "A_A") (pintype "passive"))
      (node (ref "D2") (pin "C") (pinfunction "C_C") (pintype "passive"))
      (node (ref "IC1") (pin "6") (pinfunction "P2_6") (pintype "bidirectional"))
      (node (ref "Q2") (pin "1") (pinfunction "G_1") (pintype "passive"))
      (node (ref "R2") (pin "2") (pinfunction "2_2") (pintype "passive"))
    )
    (net (code "49") (name "OUT_SRA") (class "Default")
      (node (ref "IC1") (pin "7") (pinfunction "P3_7") (pintype "bidirectional"))
      (node (ref "Q4") (pin "1") (pinfunction "G_1") (pintype "passive"))
      (node (ref "R5") (pin "2") (pinfunction "2_2") (pintype "passive"))
    )
    (net (code "50") (name "PROG_RST") (class "Default")
      (node (ref "D8") (pin "C") (pinfunction "C_C") (pintype "passive"))
      (node (ref "IC1") (pin "12") (pinfunction "P7_12") (pintype "bidirectional"))
    )
    (net (code "51") (name "SPI2_CLK") (class "Default")
      (node (ref "X4") (pin "13") (pinfunction "1_13") (pintype "passive"))
      (node (ref "X5") (pin "32") (pinfunction "1_32") (pintype "passive"))
    )
    (net (code "52") (name "SPI2_CSA") (class "Default")
      (node (ref "X4") (pin "9") (pinfunction "1_9") (pintype "passive"))
      (node (ref "X5") (pin "28") (pinfunction "1_28") (pintype "passive"))
    )
    (net (code "53") (name "SPI2_CSB") (class "Default")
      (node (ref "X4") (pin "12") (pinfunction "1_12") (pintype "passive"))
      (node (ref "X5") (pin "27") (pinfunction "1_27") (pintype "passive"))
    )
    (net (code "54") (name "SPI2_IRQ") (class "Default")
      (node (ref "X4") (pin "10") (pinfunction "1_10") (pintype "passive"))
      (node (ref "X5") (pin "25") (pinfunction "1_25") (pintype "passive"))
    )
    (net (code "55") (name "SPI2_MISO") (class "Default")
      (node (ref "X4") (pin "14") (pinfunction "1_14") (pintype "passive"))
      (node (ref "X5") (pin "31") (pinfunction "1_31") (pintype "passive"))
    )
    (net (code "56") (name "SPI2_MOSI") (class "Default")
      (node (ref "X4") (pin "15") (pinfunction "1_15") (pintype "passive"))
      (node (ref "X5") (pin "33") (pinfunction "1_33") (pintype "passive"))
    )
    (net (code "57") (name "SPI4_CLK") (class "Default")
      (node (ref "X5") (pin "23") (pinfunction "1_23") (pintype "passive"))
      (node (ref "X6") (pin "13") (pinfunction "1_13") (pintype "passive"))
    )
    (net (code "58") (name "SPI4_CSA") (class "Default")
      (node (ref "X5") (pin "22") (pinfunction "1_22") (pintype "passive"))
      (node (ref "X6") (pin "9") (pinfunction "1_9") (pintype "passive"))
    )
    (net (code "59") (name "SPI4_CSB") (class "Default")
      (node (ref "X5") (pin "21") (pinfunction "1_21") (pintype "passive"))
      (node (ref "X6") (pin "12") (pinfunction "1_12") (pintype "passive"))
    )
    (net (code "60") (name "SPI4_IRQ") (class "Default")
      (node (ref "X5") (pin "19") (pinfunction "1_19") (pintype "passive"))
      (node (ref "X6") (pin "10") (pinfunction "1_10") (pintype "passive"))
    )
    (net (code "61") (name "SPI4_MISO") (class "Default")
      (node (ref "X5") (pin "24") (pinfunction "1_24") (pintype "passive"))
      (node (ref "X6") (pin "14") (pinfunction "1_14") (pintype "passive"))
    )
    (net (code "62") (name "SPI4_MOSI") (class "Default")
      (node (ref "X5") (pin "26") (pinfunction "1_26") (pintype "passive"))
      (node (ref "X6") (pin "15") (pinfunction "1_15") (pintype "passive"))
    )
    (net (code "63") (name "SPI5_CLK") (class "Default")
      (node (ref "X5") (pin "17") (pinfunction "1_17") (pintype "passive"))
      (node (ref "X8") (pin "13") (pinfunction "1_13") (pintype "passive"))
    )
    (net (code "64") (name "SPI5_CSA") (class "Default")
      (node (ref "X5") (pin "11") (pinfunction "1_11") (pintype "passive"))
      (node (ref "X8") (pin "9") (pinfunction "1_9") (pintype "passive"))
    )
    (net (code "65") (name "SPI5_CSB") (class "Default")
      (node (ref "X5") (pin "13") (pinfunction "1_13") (pintype "passive"))
      (node (ref "X8") (pin "12") (pinfunction "1_12") (pintype "passive"))
    )
    (net (code "66") (name "SPI5_IRQ") (class "Default")
      (node (ref "X5") (pin "9") (pinfunction "1_9") (pintype "passive"))
      (node (ref "X8") (pin "10") (pinfunction "1_10") (pintype "passive"))
    )
    (net (code "67") (name "SPI5_MISO") (class "Default")
      (node (ref "X5") (pin "18") (pinfunction "1_18") (pintype "passive"))
      (node (ref "X8") (pin "14") (pinfunction "1_14") (pintype "passive"))
    )
    (net (code "68") (name "SPI5_MOSI") (class "Default")
      (node (ref "X5") (pin "20") (pinfunction "1_20") (pintype "passive"))
      (node (ref "X8") (pin "15") (pinfunction "1_15") (pintype "passive"))
    )
    (net (code "69") (name "UART_RX") (class "Default")
      (node (ref "X4") (pin "27") (pinfunction "1_27") (pintype "passive"))
      (node (ref "X5") (pin "3") (pinfunction "1_3") (pintype "passive"))
      (node (ref "X6") (pin "27") (pinfunction "1_27") (pintype "passive"))
      (node (ref "X8") (pin "27") (pinfunction "1_27") (pintype "passive"))
    )
    (net (code "70") (name "UART_TX") (class "Default")
      (node (ref "X4") (pin "28") (pinfunction "1_28") (pintype "passive"))
      (node (ref "X5") (pin "4") (pinfunction "1_4") (pintype "passive"))
      (node (ref "X6") (pin "28") (pinfunction "1_28") (pintype "passive"))
      (node (ref "X8") (pin "28") (pinfunction "1_28") (pintype "passive"))
    )
    (net (code "71") (name "unconnected-(IC1-~{INT}-Pad13)") (class "Default")
      (node (ref "IC1") (pin "13") (pinfunction "~{INT}_13") (pintype "output"))
    )
    (net (code "72") (name "unconnected-(K3A-S-Pad12A)") (class "Default")
      (node (ref "K3") (pin "12A") (pinfunction "S_12A") (pintype "passive"))
    )
    (net (code "73") (name "unconnected-(K3B-S-Pad12B)") (class "Default")
      (node (ref "K3") (pin "12B") (pinfunction "S_12B") (pintype "passive"))
    )
    (net (code "74") (name "unconnected-(K4A-S-Pad12A)") (class "Default")
      (node (ref "K4") (pin "12A") (pinfunction "S_12A") (pintype "passive"))
    )
    (net (code "75") (name "unconnected-(X4M-1-Pad20)") (class "Default")
      (node (ref "X4") (pin "20") (pinfunction "1_20") (pintype "passive"))
    )
    (net (code "76") (name "unconnected-(X6M-1-Pad20)") (class "Default")
      (node (ref "X6") (pin "20") (pinfunction "1_20") (pintype "passive"))
    )
    (net (code "77") (name "unconnected-(X7D-1-Pad4)") (class "Default")
      (node (ref "X7") (pin "4") (pinfunction "1_4") (pintype "passive"))
    )
    (net (code "78") (name "unconnected-(X7E-1-Pad5)") (class "Default")
      (node (ref "X7") (pin "5") (pinfunction "1_5") (pintype "passive"))
    )
    (net (code "79") (name "unconnected-(X8M-1-Pad20)") (class "Default")
      (node (ref "X8") (pin "20") (pinfunction "1_20") (pintype "passive"))
    )
    (net (code "80") (name "~{FAULT}") (class "Default")
      (node (ref "X4") (pin "3") (pinfunction "1_3") (pintype "passive"))
      (node (ref "X5") (pin "8") (pinfunction "1_8") (pintype "passive"))
      (node (ref "X6") (pin "3") (pinfunction "1_3") (pintype "passive"))
      (node (ref "X8") (pin "3") (pinfunction "1_3") (pintype "passive"))
    )
    (net (code "81") (name "~{MRESET}") (class "Default")
      (node (ref "D9") (pin "C") (pinfunction "C_C") (pintype "passive"))
      (node (ref "X5") (pin "6") (pinfunction "1_6") (pintype "passive"))
    )
    (net (code "82") (name "~{RESET}") (class "Default")
      (node (ref "C2") (pin "1") (pinfunction "1_1") (pintype "passive"))
      (node (ref "D8") (pin "A") (pinfunction "A_A") (pintype "passive"))
      (node (ref "D9") (pin "A") (pinfunction "A_A") (pintype "passive"))
      (node (ref "R11") (pin "2") (pinfunction "2_2") (pintype "passive"))
      (node (ref "X4") (pin "4") (pinfunction "1_4") (pintype "passive"))
      (node (ref "X6") (pin "4") (pinfunction "1_4") (pintype "passive"))
      (node (ref "X8") (pin "4") (pinfunction "1_4") (pintype "passive"))
    )
  )
)
